# boarduino_clone.net
KiCad netlist of a schematic drawn in EAGLE
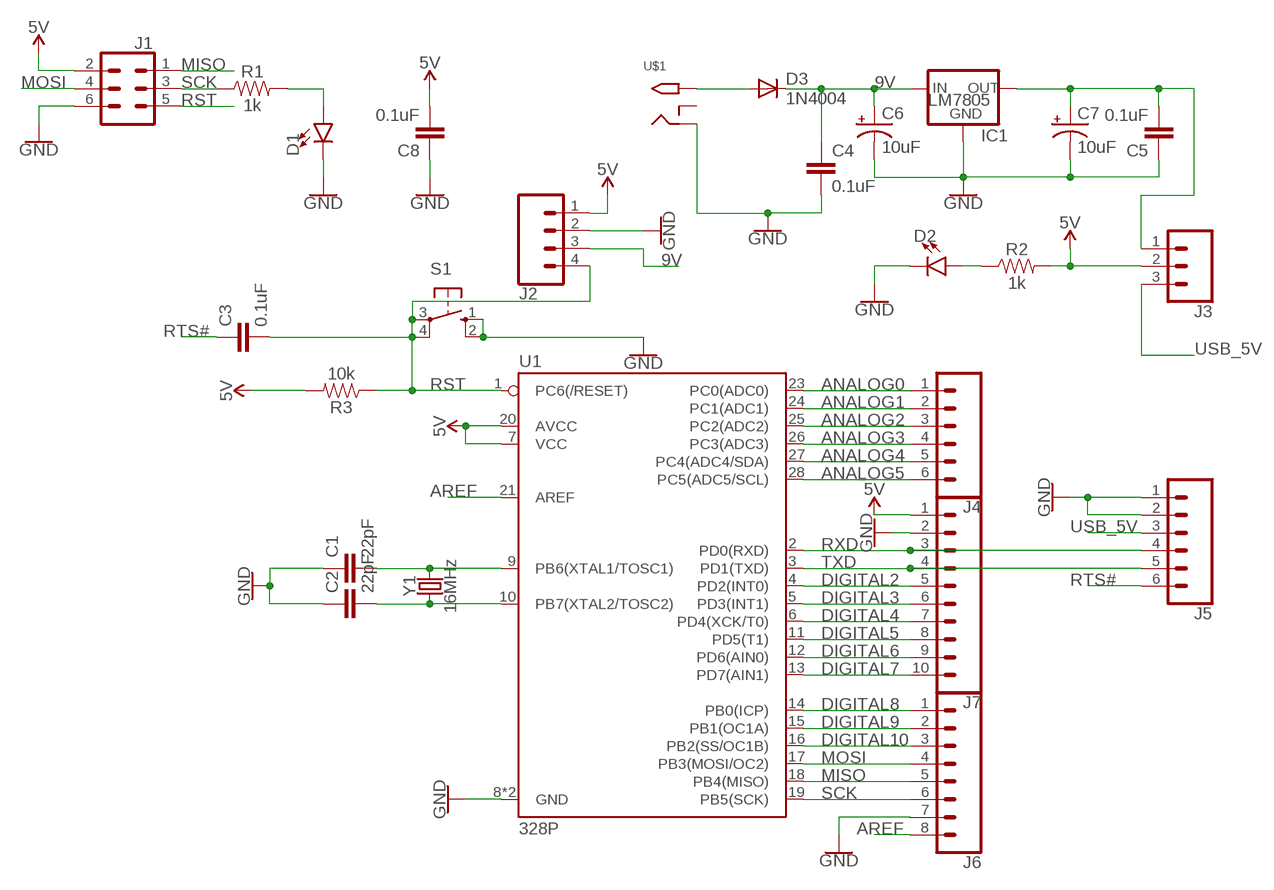
[diagram p0: schematic, sheet 1]

(export (version "E")
  (design (tool "Eeschema 10.0.6"))
  (components
    (comp (ref "C1")
      (value "22pF")
      (footprint "eagle-import:CAP-PTH-2.54")
      (libsource (lib "eagle-import") (part "22PF-PTH-2.54MM-200V-5%"))
    )
    (comp (ref "C2")
      (value "22pF")
      (footprint "eagle-import:CAP-PTH-2.54")
      (libsource (lib "eagle-import") (part "22PF-PTH-2.54MM-200V-5%"))
    )
    (comp (ref "C3")
      (value "0.1uF")
      (footprint "eagle-import:CAP-PTH-SMALL-KIT")
      (libsource (lib "eagle-import") (part "0.1UF-KIT-EZ-50V-20%"))
    )
    (comp (ref "C4")
      (value "0.1uF")
      (footprint "eagle-import:CAP-PTH-SMALL-KIT")
      (libsource (lib "eagle-import") (part "0.1UF-KIT-EZ-50V-20%"))
    )
    (comp (ref "C5")
      (value "0.1uF")
      (footprint "eagle-import:CAP-PTH-SMALL-KIT")
      (libsource (lib "eagle-import") (part "0.1UF-KIT-EZ-50V-20%"))
    )
    (comp (ref "C6")
      (value "10uF")
      (footprint "eagle-import:CPOL-RADIAL-2.5MM-5MM")
      (libsource (lib "eagle-import") (part "10UF-POLAR-RADIAL-2.5MM-25V-20%"))
    )
    (comp (ref "C7")
      (value "10uF")
      (footprint "eagle-import:CPOL-RADIAL-2.5MM-5MM")
      (libsource (lib "eagle-import") (part "10UF-POLAR-RADIAL-2.5MM-25V-20%"))
    )
    (comp (ref "C8")
      (value "0.1uF")
      (footprint "eagle-import:CAP-PTH-SMALL-KIT")
      (libsource (lib "eagle-import") (part "0.1UF-KIT-EZ-50V-20%"))
    )
    (comp (ref "D1")
      (value "LED5MM")
      (footprint "eagle-import:LED_5MM")
      (libsource (lib "eagle-import") (part "LED5MM"))
    )
    (comp (ref "D2")
      (value "LED5MM")
      (footprint "eagle-import:LED_5MM")
      (libsource (lib "eagle-import") (part "LED5MM"))
    )
    (comp (ref "D3")
      (value "1N4004")
      (footprint "eagle-import:DO41-10")
      (libsource (lib "eagle-import") (part "1N4004"))
    )
    (comp (ref "IC1")
      (value "LM7805")
      (footprint "eagle-import:78XXS")
      (libsource (lib "eagle-import") (part "78XXS"))
    )
    (comp (ref "J1")
      (value "FEMALE 2x3")
      (footprint "eagle-import:2X3")
      (libsource (lib "eagle-import") (part "CONN_03X2FEMALE"))
    )
    (comp (ref "J2")
      (value "CONN_041X04_NO_SILK")
      (footprint "eagle-import:1X04_NO_SILK")
      (libsource (lib "eagle-import") (part "CONN_041X04_NO_SILK"))
    )
    (comp (ref "J3")
      (value "CONN_031X03_NO_SILK")
      (footprint "eagle-import:1X03_NO_SILK")
      (libsource (lib "eagle-import") (part "CONN_031X03_NO_SILK"))
    )
    (comp (ref "J4")
      (value "CONN_06NO_SILK_FEMALE_PTH")
      (footprint "eagle-import:1X06_NO_SILK")
      (libsource (lib "eagle-import") (part "CONN_06NO_SILK_FEMALE_PTH"))
    )
    (comp (ref "J5")
      (value "CONN_06NO_SILK_FEMALE_PTH")
      (footprint "eagle-import:1X06_NO_SILK")
      (libsource (lib "eagle-import") (part "CONN_06NO_SILK_FEMALE_PTH"))
    )
    (comp (ref "J6")
      (value "CONN_08NO_SILK_FEMALE_PTH")
      (footprint "eagle-import:1X08_NO_SILK")
      (libsource (lib "eagle-import") (part "CONN_08NO_SILK_FEMALE_PTH"))
    )
    (comp (ref "J7")
      (value "CONN_10NO_SILK_PTH_FEMALE")
      (footprint "eagle-import:1X10_NO_SILK")
      (libsource (lib "eagle-import") (part "CONN_10NO_SILK_PTH_FEMALE"))
    )
    (comp (ref "R1")
      (value "1k")
      (footprint "eagle-import:AXIAL-0.1")
      (libsource (lib "eagle-import") (part "1KOHM-VERT-1/4W-5%"))
    )
    (comp (ref "R2")
      (value "1k")
      (footprint "eagle-import:AXIAL-0.1")
      (libsource (lib "eagle-import") (part "1KOHM-VERT-1/4W-5%"))
    )
    (comp (ref "R3")
      (value "10k")
      (footprint "eagle-import:AXIAL-0.1")
      (libsource (lib "eagle-import") (part "10KOHM-VERT-1/4W-5%"))
    )
    (comp (ref "S1")
      (value "10-XX")
      (footprint "eagle-import:B3F-10XX")
      (fields (field (name "MPN") "B3F-1000"))
      (libsource (lib "eagle-import") (part "10-XX"))
    )
    (comp (ref "U$1")
      (value "2.1MMJACKTHM")
      (footprint "eagle-import:PJ-102A")
      (libsource (lib "eagle-import") (part "2.1MMJACKTHM"))
    )
    (comp (ref "U1")
      (value "328P")
      (footprint "eagle-import:DIP28")
      (libsource (lib "eagle-import") (part "ATMEGA328P_PDIP"))
    )
    (comp (ref "Y1")
      (value "16MHz")
      (footprint "eagle-import:HC49US")
      (libsource (lib "eagle-import") (part "CRYSTAL-16MHZPTH-HC49US"))
    )
  )
  (nets
    (net (code "1") (name "/9V") (class "Default")
      (node (ref "C4") (pin "1") (pinfunction "1_1") (pintype "passive"))
      (node (ref "C6") (pin "1") (pinfunction "+_1") (pintype "passive"))
      (node (ref "D3") (pin "C") (pinfunction "C_C") (pintype "passive"))
      (node (ref "IC1") (pin "IN") (pinfunction "IN_IN") (pintype "input"))
      (node (ref "J2") (pin "3") (pinfunction "3_3") (pintype "passive"))
    )
    (net (code "2") (name "/ANALOG0") (class "Default")
      (node (ref "J4") (pin "1") (pinfunction "1_1") (pintype "passive"))
      (node (ref "U1") (pin "23") (pinfunction "PC0(ADC0)_23") (pintype "bidirectional"))
    )
    (net (code "3") (name "/ANALOG1") (class "Default")
      (node (ref "J4") (pin "2") (pinfunction "2_2") (pintype "passive"))
      (node (ref "U1") (pin "24") (pinfunction "PC1(ADC1)_24") (pintype "bidirectional"))
    )
    (net (code "4") (name "/ANALOG2") (class "Default")
      (node (ref "J4") (pin "3") (pinfunction "3_3") (pintype "passive"))
      (node (ref "U1") (pin "25") (pinfunction "PC2(ADC2)_25") (pintype "bidirectional"))
    )
    (net (code "5") (name "/ANALOG3") (class "Default")
      (node (ref "J4") (pin "4") (pinfunction "4_4") (pintype "passive"))
      (node (ref "U1") (pin "26") (pinfunction "PC3(ADC3)_26") (pintype "bidirectional"))
    )
    (net (code "6") (name "/ANALOG4") (class "Default")
      (node (ref "J4") (pin "5") (pinfunction "5_5") (pintype "passive"))
      (node (ref "U1") (pin "27") (pinfunction "PC4(ADC4/SDA)_27") (pintype "bidirectional"))
    )
    (net (code "7") (name "/ANALOG5") (class "Default")
      (node (ref "J4") (pin "6") (pinfunction "6_6") (pintype "passive"))
      (node (ref "U1") (pin "28") (pinfunction "PC5(ADC5/SCL)_28") (pintype "bidirectional"))
    )
    (net (code "8") (name "/AREF") (class "Default")
      (node (ref "J6") (pin "8") (pinfunction "8_8") (pintype "passive"))
      (node (ref "U1") (pin "21") (pinfunction "AREF_21") (pintype "bidirectional"))
    )
    (net (code "9") (name "/DIGITAL2") (class "Default")
      (node (ref "J7") (pin "5") (pinfunction "5_5") (pintype "passive"))
      (node (ref "U1") (pin "4") (pinfunction "PD2(INT0)_4") (pintype "bidirectional"))
    )
    (net (code "10") (name "/DIGITAL3") (class "Default")
      (node (ref "J7") (pin "6") (pinfunction "6_6") (pintype "passive"))
      (node (ref "U1") (pin "5") (pinfunction "PD3(INT1)_5") (pintype "bidirectional"))
    )
    (net (code "11") (name "/DIGITAL4") (class "Default")
      (node (ref "J7") (pin "7") (pinfunction "7_7") (pintype "passive"))
      (node (ref "U1") (pin "6") (pinfunction "PD4(XCK/T0)_6") (pintype "bidirectional"))
    )
    (net (code "12") (name "/DIGITAL5") (class "Default")
      (node (ref "J7") (pin "8") (pinfunction "8_8") (pintype "passive"))
      (node (ref "U1") (pin "11") (pinfunction "PD5(T1)_11") (pintype "bidirectional"))
    )
    (net (code "13") (name "/DIGITAL6") (class "Default")
      (node (ref "J7") (pin "9") (pinfunction "9_9") (pintype "passive"))
      (node (ref "U1") (pin "12") (pinfunction "PD6(AIN0)_12") (pintype "bidirectional"))
    )
    (net (code "14") (name "/DIGITAL7") (class "Default")
      (node (ref "J7") (pin "10") (pinfunction "10_10") (pintype "passive"))
      (node (ref "U1") (pin "13") (pinfunction "PD7(AIN1)_13") (pintype "bidirectional"))
    )
    (net (code "15") (name "/DIGITAL8") (class "Default")
      (node (ref "J6") (pin "1") (pinfunction "1_1") (pintype "passive"))
      (node (ref "U1") (pin "14") (pinfunction "PB0(ICP)_14") (pintype "bidirectional"))
    )
    (net (code "16") (name "/DIGITAL9") (class "Default")
      (node (ref "J6") (pin "2") (pinfunction "2_2") (pintype "passive"))
      (node (ref "U1") (pin "15") (pinfunction "PB1(OC1A)_15") (pintype "bidirectional"))
    )
    (net (code "17") (name "/DIGITAL10") (class "Default")
      (node (ref "J6") (pin "3") (pinfunction "3_3") (pintype "passive"))
      (node (ref "U1") (pin "16") (pinfunction "PB2(SS/OC1B)_16") (pintype "bidirectional"))
    )
    (net (code "18") (name "/MISO") (class "Default")
      (node (ref "J1") (pin "1") (pinfunction "1_1") (pintype "bidirectional"))
      (node (ref "J6") (pin "5") (pinfunction "5_5") (pintype "passive"))
      (node (ref "U1") (pin "18") (pinfunction "PB4(MISO)_18") (pintype "bidirectional"))
    )
    (net (code "19") (name "/MOSI") (class "Default")
      (node (ref "J1") (pin "4") (pinfunction "4_4") (pintype "bidirectional"))
      (node (ref "J6") (pin "4") (pinfunction "4_4") (pintype "passive"))
      (node (ref "U1") (pin "17") (pinfunction "PB3(MOSI/OC2)_17") (pintype "bidirectional"))
    )
    (net (code "20") (name "/RST") (class "Default")
      (node (ref "C3") (pin "2") (pinfunction "2_2") (pintype "passive"))
      (node (ref "J1") (pin "5") (pinfunction "5_5") (pintype "bidirectional"))
      (node (ref "J2") (pin "4") (pinfunction "4_4") (pintype "passive"))
      (node (ref "R3") (pin "P$1") (pinfunction "1_P$1") (pintype "passive"))
      (node (ref "S1") (pin "3") (pinfunction "P_3") (pintype "passive"))
      (node (ref "S1") (pin "4") (pinfunction "P1_4") (pintype "passive"))
      (node (ref "U1") (pin "1") (pinfunction "PC6(/RESET)_1") (pintype "bidirectional"))
    )
    (net (code "21") (name "/RTS#") (class "Default")
      (node (ref "C3") (pin "1") (pinfunction "1_1") (pintype "passive"))
      (node (ref "J5") (pin "6") (pinfunction "6_6") (pintype "passive"))
    )
    (net (code "22") (name "/RXD") (class "Default")
      (node (ref "J5") (pin "4") (pinfunction "4_4") (pintype "passive"))
      (node (ref "J7") (pin "3") (pinfunction "3_3") (pintype "passive"))
      (node (ref "U1") (pin "2") (pinfunction "PD0(RXD)_2") (pintype "bidirectional"))
    )
    (net (code "23") (name "/SCK") (class "Default")
      (node (ref "J1") (pin "3") (pinfunction "3_3") (pintype "bidirectional"))
      (node (ref "J6") (pin "6") (pinfunction "6_6") (pintype "passive"))
      (node (ref "R1") (pin "P$1") (pinfunction "1_P$1") (pintype "passive"))
      (node (ref "U1") (pin "19") (pinfunction "PB5(SCK)_19") (pintype "bidirectional"))
    )
    (net (code "24") (name "/TXD") (class "Default")
      (node (ref "J5") (pin "5") (pinfunction "5_5") (pintype "passive"))
      (node (ref "J7") (pin "4") (pinfunction "4_4") (pintype "passive"))
      (node (ref "U1") (pin "3") (pinfunction "PD1(TXD)_3") (pintype "bidirectional"))
    )
    (net (code "25") (name "/USB_5V") (class "Default")
      (node (ref "J3") (pin "3") (pinfunction "3_3") (pintype "passive"))
      (node (ref "J5") (pin "3") (pinfunction "3_3") (pintype "passive"))
    )
    (net (code "26") (name "5V") (class "Default")
      (node (ref "C8") (pin "2") (pinfunction "2_2") (pintype "passive"))
      (node (ref "J1") (pin "2") (pinfunction "2_2") (pintype "bidirectional"))
      (node (ref "J2") (pin "1") (pinfunction "1_1") (pintype "passive"))
      (node (ref "J3") (pin "2") (pinfunction "2_2") (pintype "passive"))
      (node (ref "J7") (pin "1") (pinfunction "1_1") (pintype "passive"))
      (node (ref "R2") (pin "P$2") (pinfunction "2_P$2") (pintype "passive"))
      (node (ref "R3") (pin "P$2") (pinfunction "2_P$2") (pintype "passive"))
      (node (ref "U1") (pin "20") (pinfunction "AVCC_20") (pintype "bidirectional"))
      (node (ref "U1") (pin "7") (pinfunction "VCC_7") (pintype "bidirectional"))
    )
    (net (code "27") (name "GND") (class "Default")
      (node (ref "C1") (pin "1") (pinfunction "1_1") (pintype "passive"))
      (node (ref "C2") (pin "1") (pinfunction "1_1") (pintype "passive"))
      (node (ref "C4") (pin "2") (pinfunction "2_2") (pintype "passive"))
      (node (ref "C5") (pin "1") (pinfunction "1_1") (pintype "passive"))
      (node (ref "C6") (pin "2") (pinfunction "-_2") (pintype "passive"))
      (node (ref "C7") (pin "2") (pinfunction "-_2") (pintype "passive"))
      (node (ref "C8") (pin "1") (pinfunction "1_1") (pintype "passive"))
      (node (ref "D1") (pin "K") (pinfunction "C_K") (pintype "passive"))
      (node (ref "D2") (pin "K") (pinfunction "C_K") (pintype "passive"))
      (node (ref "IC1") (pin "GND") (pinfunction "GND_GND") (pintype "input"))
      (node (ref "J1") (pin "6") (pinfunction "6_6") (pintype "bidirectional"))
      (node (ref "J2") (pin "2") (pinfunction "2_2") (pintype "passive"))
      (node (ref "J5") (pin "1") (pinfunction "1_1") (pintype "passive"))
      (node (ref "J5") (pin "2") (pinfunction "2_2") (pintype "passive"))
      (node (ref "J6") (pin "7") (pinfunction "7_7") (pintype "passive"))
      (node (ref "J7") (pin "2") (pinfunction "2_2") (pintype "passive"))
      (node (ref "S1") (pin "1") (pinfunction "S_1") (pintype "passive"))
      (node (ref "S1") (pin "2") (pinfunction "S1_2") (pintype "passive"))
      (node (ref "U$1") (pin "RING") (pinfunction "RING_RING") (pintype "bidirectional"))
      (node (ref "U1") (pin "22") (pinfunction "GND_22") (pintype "bidirectional"))
      (node (ref "U1") (pin "8") (pinfunction "GND_8") (pintype "bidirectional"))
    )
    (net (code "28") (name "Net-(C7-+)") (class "Default")
      (node (ref "C5") (pin "2") (pinfunction "2_2") (pintype "passive"))
      (node (ref "C7") (pin "1") (pinfunction "+_1") (pintype "passive"))
      (node (ref "IC1") (pin "OUT") (pinfunction "OUT_OUT") (pintype "passive"))
      (node (ref "J3") (pin "1") (pinfunction "1_1") (pintype "passive"))
    )
    (net (code "29") (name "Net-(D3-PadA)") (class "Default")
      (node (ref "D3") (pin "A") (pinfunction "A_A") (pintype "passive"))
      (node (ref "U$1") (pin "TIP") (pinfunction "TIP_TIP") (pintype "bidirectional"))
    )
    (net (code "30") (name "Net-(R1-2)") (class "Default")
      (node (ref "D1") (pin "A") (pinfunction "A_A") (pintype "passive"))
      (node (ref "R1") (pin "P$2") (pinfunction "2_P$2") (pintype "passive"))
    )
    (net (code "31") (name "Net-(R2-1)") (class "Default")
      (node (ref "D2") (pin "A") (pinfunction "A_A") (pintype "passive"))
      (node (ref "R2") (pin "P$1") (pinfunction "1_P$1") (pintype "passive"))
    )
    (net (code "32") (name "Net-(U1-PB6(XTAL1{slash}TOSC1))") (class "Default")
      (node (ref "C1") (pin "2") (pinfunction "2_2") (pintype "passive"))
      (node (ref "U1") (pin "9") (pinfunction "PB6(XTAL1/TOSC1)_9") (pintype "bidirectional"))
      (node (ref "Y1") (pin "2") (pinfunction "2_2") (pintype "passive"))
    )
    (net (code "33") (name "Net-(U1-PB7(XTAL2{slash}TOSC2))") (class "Default")
      (node (ref "C2") (pin "2") (pinfunction "2_2") (pintype "passive"))
      (node (ref "U1") (pin "10") (pinfunction "PB7(XTAL2/TOSC2)_10") (pintype "bidirectional"))
      (node (ref "Y1") (pin "1") (pinfunction "1_1") (pintype "passive"))
    )
    (net (code "34") (name "unconnected-(U$1-PadRING_SW)") (class "Default")
      (node (ref "U$1") (pin "RING_SW") (pinfunction "RING_SW_RING_SW") (pintype "bidirectional"))
    )
  )
)
